# FSK_Receiver.net
KiCad netlist of a schematic drawn in Altium Designer
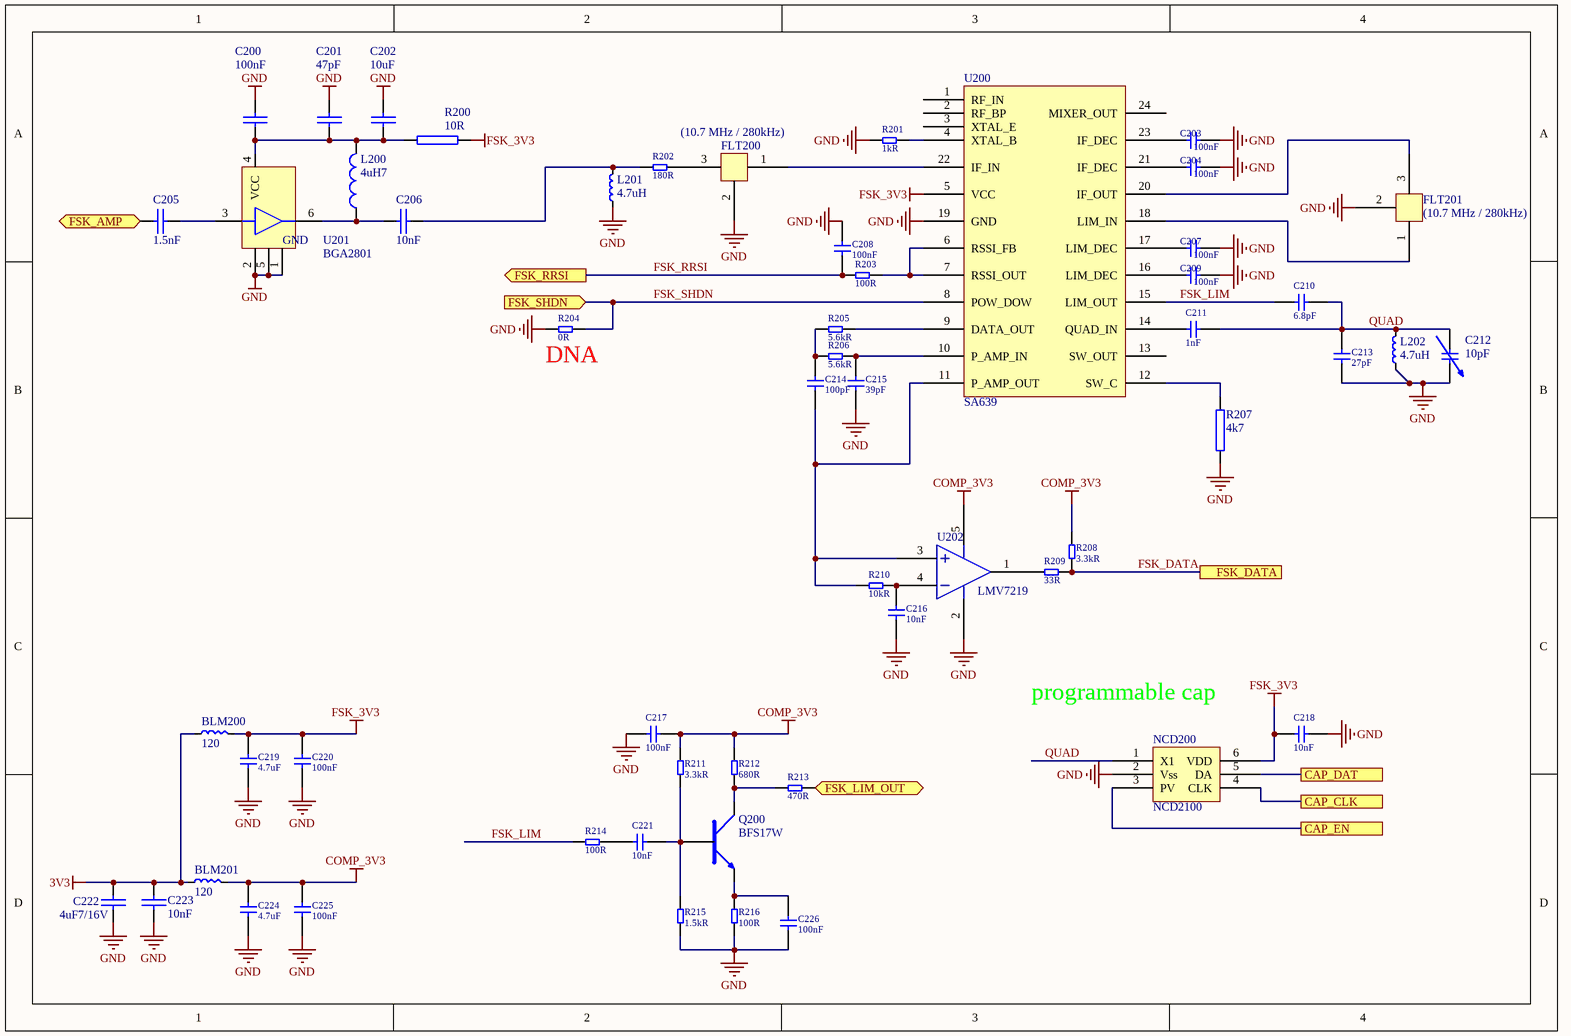
[diagram p0: FSK_Receiver.SchDoc]

(export (version "E")
  (design (tool "Eeschema 10.0.6"))
  (components
    (comp (ref "BLM200")
      (value "FerriteBeat")
      (footprint "BLM18SG121TN1")
      (description "BLM18SG121TN1")
      (fields (field (name "ALTIUM_UNNAMED_1") "120"))
      (libsource (lib "zynq_board") (part "FerriteBeat"))
    )
    (comp (ref "BLM201")
      (value "FerriteBeat")
      (footprint "BLM18SG121TN1")
      (description "BLM18SG121TN1")
      (fields (field (name "ALTIUM_UNNAMED_1") "120"))
      (libsource (lib "zynq_board") (part "FerriteBeat"))
    )
    (comp (ref "C200") (value "100nF") (footprint "0402RN") (libsource (lib "*") (part "_C")))
    (comp (ref "C201") (value "47pF") (footprint "0402RN") (libsource (lib "*") (part "_C")))
    (comp (ref "C202")
      (value "10uF")
      (footprint "0603R")
      (description "MLCC, X5R, 16V, 20%, 0603")
      (fields
        (field (name "PART NUMBER") "10u, 0603, 16V, X5R, 20%")
        (field (name "SOURCE") "SN29500-4, Tabelle 1")
      )
      (libsource (lib "Symeo_libs") (part "_CAP"))
    )
    (comp (ref "C203")
      (value "100nF")
      (footprint "C_SMD_0402")
      (description "100nF, 0402, 6.3V, 10%, X5R")
      (fields (field (name "Comment") "SMD capacitor"))
      (libsource (lib "zynq_board") (part "C_SMD"))
    )
    (comp (ref "C204")
      (value "100nF")
      (footprint "C_SMD_0402")
      (description "100nF, 0402, 6.3V, 10%, X5R")
      (fields (field (name "Comment") "SMD capacitor"))
      (libsource (lib "zynq_board") (part "C_SMD"))
    )
    (comp (ref "C205") (value "1.5nF") (footprint "0402RN") (libsource (lib "*") (part "_C")))
    (comp (ref "C206") (value "10nF") (footprint "0402RN") (libsource (lib "*") (part "_C")))
    (comp (ref "C207")
      (value "100nF")
      (footprint "C_SMD_0402")
      (description "100nF, 0402, 6.3V, 10%, X5R")
      (fields (field (name "Comment") "SMD capacitor"))
      (libsource (lib "zynq_board") (part "C_SMD"))
    )
    (comp (ref "C208")
      (value "100nF")
      (footprint "C_SMD_0402")
      (description "100nF, 0402, 6.3V, 10%, X5R")
      (fields (field (name "Comment") "SMD capacitor"))
      (libsource (lib "zynq_board") (part "C_SMD"))
    )
    (comp (ref "C209")
      (value "100nF")
      (footprint "C_SMD_0402")
      (description "100nF, 0402, 6.3V, 10%, X5R")
      (fields (field (name "Comment") "SMD capacitor"))
      (libsource (lib "zynq_board") (part "C_SMD"))
    )
    (comp (ref "C210")
      (value "6.8pF")
      (footprint "C_SMD_0402")
      (description "6.8pF, 0402, 6.3V, 10%, X5R")
      (fields (field (name "Comment") "SMD capacitor"))
      (libsource (lib "zynq_board") (part "C_SMD"))
    )
    (comp (ref "C211")
      (value "1nF")
      (footprint "C_SMD_0402")
      (description "1nF, 0402, 6.3V, 10%, X5R")
      (fields (field (name "Comment") "SMD capacitor"))
      (libsource (lib "zynq_board") (part "C_SMD"))
    )
    (comp (ref "C212")
      (value "10pF")
      (footprint "TZC03")
      (description "TZC03R100A110")
      (libsource (lib "zynq_board") (part "TZC03R100A110"))
    )
    (comp (ref "C213")
      (value "27pF")
      (footprint "C_SMD_0402")
      (description "28pF, 0402, 6.3V, 1%, X5R")
      (fields (field (name "Comment") "SMD capacitor"))
      (libsource (lib "zynq_board") (part "C_SMD"))
    )
    (comp (ref "C214")
      (value "100pF")
      (footprint "C_SMD_0402")
      (description "100pF, 0402, 6.3V, 10%, X5R")
      (fields (field (name "Comment") "SMD capacitor"))
      (libsource (lib "zynq_board") (part "C_SMD"))
    )
    (comp (ref "C215")
      (value "39pF")
      (footprint "C_SMD_0402")
      (description "39pF, 0402, 6.3V, 10%, X5R")
      (fields (field (name "Comment") "SMD capacitor"))
      (libsource (lib "zynq_board") (part "C_SMD"))
    )
    (comp (ref "C216")
      (value "10nF")
      (footprint "C_SMD_0402")
      (description "10nF, 0402, 6.3V, 10%, X5R")
      (fields (field (name "Comment") "SMD capacitor"))
      (libsource (lib "zynq_board") (part "C_SMD"))
    )
    (comp (ref "C217")
      (value "100nF")
      (footprint "C_SMD_0402")
      (description "100nF, 0402, 6.3V, 10%, X5R")
      (fields (field (name "Comment") "SMD capacitor"))
      (libsource (lib "zynq_board") (part "C_SMD"))
    )
    (comp (ref "C218")
      (value "10nF")
      (footprint "C_SMD_0402")
      (description "10nF, 0402, 6.3V, 10%, X5R")
      (fields (field (name "Comment") "SMD capacitor"))
      (libsource (lib "zynq_board") (part "C_SMD"))
    )
    (comp (ref "C219")
      (value "4.7uF")
      (footprint "C_SMD_0603")
      (description "4.7uF, 0603, 6.3V, 10%, X5R")
      (fields (field (name "Comment") "SMD capacitor"))
      (libsource (lib "zynq_board") (part "C_SMD"))
    )
    (comp (ref "C220")
      (value "100nF")
      (footprint "C_SMD_0402")
      (description "100nF, 0402, 6.3V, 10%, X5R")
      (fields (field (name "Comment") "SMD capacitor"))
      (libsource (lib "zynq_board") (part "C_SMD"))
    )
    (comp (ref "C221")
      (value "10nF")
      (footprint "C_SMD_0402")
      (description "10nF, 0402, 6.3V, 10%, X5R")
      (fields (field (name "Comment") "SMD capacitor"))
      (libsource (lib "zynq_board") (part "C_SMD"))
    )
    (comp (ref "C222")
      (value "4uF7/16V")
      (footprint "1206R")
      (description "MLCC, 1206, X7R, 16V, 20%")
      (fields (field (name "PART NUMBER") "4u7, 1206, 16V, X7R"))
      (libsource (lib "Symeo_libs") (part "_CAP"))
    )
    (comp (ref "C223")
      (value "10nF")
      (footprint "0402RN")
      (description "MLCC, X7R, 50V, 10%, 0402")
      (fields (field (name "PART NUMBER") "10n, 0402, 50V, X7R"))
      (libsource (lib "Symeo_libs") (part "_CAP"))
    )
    (comp (ref "C224")
      (value "4.7uF")
      (footprint "C_SMD_0603")
      (description "4.7uF, 0603, 6.3V, 10%, X5R")
      (fields (field (name "Comment") "SMD capacitor"))
      (libsource (lib "zynq_board") (part "C_SMD"))
    )
    (comp (ref "C225")
      (value "100nF")
      (footprint "C_SMD_0402")
      (description "100nF, 0402, 6.3V, 10%, X5R")
      (fields (field (name "Comment") "SMD capacitor"))
      (libsource (lib "zynq_board") (part "C_SMD"))
    )
    (comp (ref "C226")
      (value "100nF")
      (footprint "C_SMD_0402")
      (description "100nF, 0402, 6.3V, 10%, X5R")
      (fields (field (name "Comment") "SMD capacitor"))
      (libsource (lib "zynq_board") (part "C_SMD"))
    )
    (comp (ref "FLT200")
      (value "(10.7 MHz / 280kHz)")
      (footprint "Cerafil_10.7MHz_Filter")
      (description "Murata SFECV10M7FA00-R0")
      (libsource (lib "zynq_board") (part "CERAFIL_BP_10.7MHz"))
    )
    (comp (ref "FLT201")
      (value "(10.7 MHz / 280kHz)")
      (footprint "Cerafil_10.7MHz_Filter")
      (description "Murata SFECV10M7FA00-R0")
      (libsource (lib "") (part "CERAFIL_BP_10.7MHz_1"))
    )
    (comp (ref "L200")
      (value "4uH7")
      (footprint "0805R")
      (description "Wuerth WE MI; Wuerth Nr. 7447906")
      (libsource (lib "*") (part "_L"))
    )
    (comp (ref "L201")
      (value "4.7uH")
      (footprint "WE-MI SMD Multilayer Inductor")
      (description "7447906, WE Inductor")
      (libsource (lib "zynq_board") (part "7447906_L_4u7"))
    )
    (comp (ref "L202")
      (value "4.7uH")
      (footprint "WE-MI SMD Multilayer Inductor")
      (description "7447906, WE Inductor")
      (libsource (lib "zynq_board") (part "7447906_L_4u7"))
    )
    (comp (ref "NCD200")
      (value "~")
      (footprint "NCD2100:PCBComponent_1")
      (description "NCD2100 Non-volatile Digital Programmable Capacitor SOT23-6")
      (fields (field (name "PART NUMBER") "NCD2100"))
      (libsource (lib "Symeo_libs") (part "NCD2100"))
    )
    (comp (ref "Q200")
      (value "BFS17W")
      (footprint "SOT-323")
      (description "BFS17WH6327XTSA1")
      (libsource (lib "zynq_board") (part "BFS17W"))
    )
    (comp (ref "R200") (value "10R") (footprint "0402RN") (libsource (lib "*") (part "_R")))
    (comp (ref "R201")
      (value "1kR")
      (footprint "R_SMD_0402")
      (description "1kR, 0402, 1%")
      (fields (field (name "Comment") "SMD Resistor"))
      (libsource (lib "zynq_board") (part "R_SMD"))
    )
    (comp (ref "R202")
      (value "180R")
      (footprint "R_SMD_0402")
      (description "180R. 0402, 1%")
      (fields (field (name "Comment") "SMD Resistor"))
      (libsource (lib "zynq_board") (part "R_SMD"))
    )
    (comp (ref "R203")
      (value "100R")
      (footprint "R_SMD_0402")
      (description "100R, 0402, 1%")
      (fields (field (name "Comment") "SMD Resistor"))
      (libsource (lib "zynq_board") (part "R_SMD"))
    )
    (comp (ref "R204")
      (value "0R")
      (footprint "R_SMD_0402")
      (description "0R, 0402, 1%")
      (fields (field (name "Comment") "SMD Resistor"))
      (libsource (lib "zynq_board") (part "R_SMD"))
    )
    (comp (ref "R205")
      (value "5.6kR")
      (footprint "R_SMD_0402")
      (description "5.6kR, 0402, 1%")
      (fields (field (name "Comment") "SMD Resistor"))
      (libsource (lib "zynq_board") (part "R_SMD"))
    )
    (comp (ref "R206")
      (value "5.6kR")
      (footprint "R_SMD_0402")
      (description "5.6kR, 0402, 1%")
      (fields (field (name "Comment") "SMD Resistor"))
      (libsource (lib "zynq_board") (part "R_SMD"))
    )
    (comp (ref "R207")
      (value "4k7")
      (footprint "0402RN")
      (description "1%, 0.063W, 50V, 0402")
      (fields (field (name "PART NUMBER") "4k7, 0402, 1%, 0.063W, 50V"))
      (libsource (lib "Symeo_libs") (part "_RES"))
    )
    (comp (ref "R208")
      (value "3.3kR")
      (footprint "R_SMD_0402")
      (description "3.3kR, 0402, 1%")
      (fields (field (name "Comment") "SMD Resistor"))
      (libsource (lib "zynq_board") (part "R_SMD"))
    )
    (comp (ref "R209")
      (value "33R")
      (footprint "R_SMD_0402")
      (description "33R, 0402, 1%")
      (fields (field (name "Comment") "SMD Resistor"))
      (libsource (lib "zynq_board") (part "R_SMD"))
    )
    (comp (ref "R210")
      (value "10kR")
      (footprint "R_SMD_0402")
      (description "10kR, 0402, 1%")
      (fields (field (name "Comment") "SMD Resistor"))
      (libsource (lib "zynq_board") (part "R_SMD"))
    )
    (comp (ref "R211")
      (value "3.3kR")
      (footprint "R_SMD_0402")
      (description "3.3kR, 0402, 1%")
      (fields (field (name "Comment") "SMD Resistor"))
      (libsource (lib "zynq_board") (part "R_SMD"))
    )
    (comp (ref "R212")
      (value "680R")
      (footprint "R_SMD_0402")
      (description "680R, 0402, 1%")
      (fields (field (name "Comment") "SMD Resistor"))
      (libsource (lib "zynq_board") (part "R_SMD"))
    )
    (comp (ref "R213")
      (value "470R")
      (footprint "R_SMD_0402")
      (description "470R, 0402, 1%")
      (fields (field (name "Comment") "SMD Resistor"))
      (libsource (lib "zynq_board") (part "R_SMD"))
    )
    (comp (ref "R214")
      (value "100R")
      (footprint "R_SMD_0402")
      (description "100R, 0402, 1%")
      (fields (field (name "Comment") "SMD Resistor"))
      (libsource (lib "zynq_board") (part "R_SMD"))
    )
    (comp (ref "R215")
      (value "1.5kR")
      (footprint "R_SMD_0402")
      (description "1.5kR, 0402, 1%")
      (fields (field (name "Comment") "SMD Resistor"))
      (libsource (lib "zynq_board") (part "R_SMD"))
    )
    (comp (ref "R216")
      (value "100R")
      (footprint "R_SMD_0402")
      (description "100R, 0402, 1%")
      (fields (field (name "Comment") "SMD Resistor"))
      (libsource (lib "zynq_board") (part "R_SMD"))
    )
    (comp (ref "U200")
      (value "SA639")
      (footprint "TSSOP24")
      (description "SA639DH/01,118")
      (libsource (lib "zynq_board") (part "SA639"))
    )
    (comp (ref "U201")
      (value "BGA2801")
      (footprint "SOT-363:SOT-363")
      (description "NXP BGA2801")
      (libsource (lib "AVAGO_RF") (part "ABA-32563"))
    )
    (comp (ref "U202")
      (value "LMV7219")
      (footprint "SOT-23-5")
      (description "LMV7219M5")
      (libsource (lib "zynq_board") (part "LMV7219"))
    )
  )
  (nets
    (net (code "1") (name "/CAP_CLK") (class "Default")
      (node (ref "NCD200") (pin "4") (pinfunction "CLK_4") (pintype "passive"))
    )
    (net (code "2") (name "/CAP_DAT") (class "Default")
      (node (ref "NCD200") (pin "5") (pinfunction "DA_5") (pintype "passive"))
    )
    (net (code "3") (name "/CAP_EN") (class "Default")
      (node (ref "NCD200") (pin "3") (pinfunction "PV_3") (pintype "passive"))
    )
    (net (code "4") (name "/FSK_AMP") (class "Default") (node (ref "C205") (pin "2") (pintype "passive")))
    (net (code "5") (name "/FSK_DATA") (class "Default")
      (node (ref "R208") (pin "2") (pinfunction "2_2") (pintype "passive"))
      (node (ref "R209") (pin "1") (pinfunction "1_1") (pintype "passive"))
    )
    (net (code "6") (name "/FSK_LIM") (class "Default")
      (node (ref "C210") (pin "1") (pinfunction "1_1") (pintype "passive"))
      (node (ref "R214") (pin "2") (pinfunction "2_2") (pintype "passive"))
      (node (ref "U200") (pin "15") (pinfunction "LIM_OUT_15") (pintype "passive"))
    )
    (net (code "7") (name "/FSK_LIM_OUT") (class "Default")
      (node (ref "R213") (pin "2") (pinfunction "2_2") (pintype "passive"))
    )
    (net (code "8") (name "/FSK_RRSI") (class "Default")
      (node (ref "C208") (pin "2") (pinfunction "2_2") (pintype "passive"))
      (node (ref "R203") (pin "2") (pinfunction "2_2") (pintype "passive"))
    )
    (net (code "9") (name "/FSK_SHDN") (class "Default")
      (node (ref "R204") (pin "1") (pinfunction "1_1") (pintype "passive"))
      (node (ref "U200") (pin "8") (pinfunction "POW_DOW_8") (pintype "passive"))
    )
    (net (code "10") (name "/QUAD") (class "Default")
      (node (ref "C210") (pin "2") (pinfunction "2_2") (pintype "passive"))
      (node (ref "C211") (pin "2") (pinfunction "2_2") (pintype "passive"))
      (node (ref "C212") (pin "1") (pinfunction "1_1") (pintype "passive"))
      (node (ref "C213") (pin "2") (pinfunction "2_2") (pintype "passive"))
      (node (ref "L202") (pin "1") (pinfunction "1_1") (pintype "passive"))
      (node (ref "NCD200") (pin "1") (pinfunction "X1_1") (pintype "passive"))
    )
    (net (code "11") (name "3V3") (class "Default")
      (node (ref "BLM200") (pin "2") (pinfunction "2_2") (pintype "passive"))
      (node (ref "BLM201") (pin "2") (pinfunction "2_2") (pintype "passive"))
      (node (ref "C222") (pin "1") (pintype "passive"))
      (node (ref "C223") (pin "1") (pintype "passive"))
    )
    (net (code "12") (name "COMP_3V3") (class "Default")
      (node (ref "BLM201") (pin "1") (pinfunction "1_1") (pintype "passive"))
      (node (ref "C217") (pin "2") (pinfunction "2_2") (pintype "passive"))
      (node (ref "C224") (pin "1") (pinfunction "1_1") (pintype "passive"))
      (node (ref "C225") (pin "1") (pinfunction "1_1") (pintype "passive"))
      (node (ref "R208") (pin "1") (pinfunction "1_1") (pintype "passive"))
      (node (ref "R211") (pin "1") (pinfunction "1_1") (pintype "passive"))
      (node (ref "R212") (pin "1") (pinfunction "1_1") (pintype "passive"))
      (node (ref "U202") (pin "5") (pintype "passive"))
    )
    (net (code "13") (name "FSK_3V3") (class "Default")
      (node (ref "BLM200") (pin "1") (pinfunction "1_1") (pintype "passive"))
      (node (ref "C218") (pin "2") (pinfunction "2_2") (pintype "passive"))
      (node (ref "C219") (pin "1") (pinfunction "1_1") (pintype "passive"))
      (node (ref "C220") (pin "1") (pinfunction "1_1") (pintype "passive"))
      (node (ref "NCD200") (pin "6") (pinfunction "VDD_6") (pintype "passive"))
      (node (ref "R200") (pin "2") (pintype "passive"))
      (node (ref "U200") (pin "5") (pinfunction "VCC_5") (pintype "passive"))
    )
    (net (code "14") (name "GND") (class "Default")
      (node (ref "C200") (pin "2") (pintype "passive"))
      (node (ref "C201") (pin "2") (pintype "passive"))
      (node (ref "C202") (pin "1") (pintype "passive"))
      (node (ref "C203") (pin "2") (pinfunction "2_2") (pintype "passive"))
      (node (ref "C204") (pin "2") (pinfunction "2_2") (pintype "passive"))
      (node (ref "C207") (pin "2") (pinfunction "2_2") (pintype "passive"))
      (node (ref "C208") (pin "1") (pinfunction "1_1") (pintype "passive"))
      (node (ref "C209") (pin "2") (pinfunction "2_2") (pintype "passive"))
      (node (ref "C212") (pin "2") (pinfunction "2_2") (pintype "passive"))
      (node (ref "C213") (pin "1") (pinfunction "1_1") (pintype "passive"))
      (node (ref "C215") (pin "2") (pinfunction "2_2") (pintype "passive"))
      (node (ref "C216") (pin "2") (pinfunction "2_2") (pintype "passive"))
      (node (ref "C217") (pin "1") (pinfunction "1_1") (pintype "passive"))
      (node (ref "C218") (pin "1") (pinfunction "1_1") (pintype "passive"))
      (node (ref "C219") (pin "2") (pinfunction "2_2") (pintype "passive"))
      (node (ref "C220") (pin "2") (pinfunction "2_2") (pintype "passive"))
      (node (ref "C222") (pin "2") (pintype "passive"))
      (node (ref "C223") (pin "2") (pintype "passive"))
      (node (ref "C224") (pin "2") (pinfunction "2_2") (pintype "passive"))
      (node (ref "C225") (pin "2") (pinfunction "2_2") (pintype "passive"))
      (node (ref "C226") (pin "2") (pinfunction "2_2") (pintype "passive"))
      (node (ref "FLT200") (pin "2") (pintype "passive"))
      (node (ref "FLT201") (pin "2") (pintype "passive"))
      (node (ref "L201") (pin "2") (pinfunction "2_2") (pintype "passive"))
      (node (ref "L202") (pin "2") (pinfunction "2_2") (pintype "passive"))
      (node (ref "NCD200") (pin "2") (pinfunction "Vss_2") (pintype "passive"))
      (node (ref "R201") (pin "2") (pinfunction "2_2") (pintype "passive"))
      (node (ref "R204") (pin "2") (pinfunction "2_2") (pintype "passive"))
      (node (ref "R207") (pin "1") (pintype "passive"))
      (node (ref "R215") (pin "2") (pinfunction "2_2") (pintype "passive"))
      (node (ref "R216") (pin "2") (pinfunction "2_2") (pintype "passive"))
      (node (ref "U200") (pin "19") (pinfunction "GND_19") (pintype "passive"))
      (node (ref "U201") (pin "1") (pintype "passive"))
      (node (ref "U201") (pin "2") (pintype "passive"))
      (node (ref "U201") (pin "5") (pintype "passive"))
      (node (ref "U202") (pin "2") (pintype "passive"))
    )
    (net (code "15") (name "Net-(C203-Pad1)") (class "Default")
      (node (ref "C203") (pin "1") (pinfunction "1_1") (pintype "passive"))
      (node (ref "U200") (pin "23") (pinfunction "IF_DEC_23") (pintype "passive"))
    )
    (net (code "16") (name "Net-(C204-Pad1)") (class "Default")
      (node (ref "C204") (pin "1") (pinfunction "1_1") (pintype "passive"))
      (node (ref "U200") (pin "21") (pinfunction "IF_DEC_21") (pintype "passive"))
    )
    (net (code "17") (name "Net-(C205-Pad1)") (class "Default")
      (node (ref "C205") (pin "1") (pintype "passive"))
      (node (ref "U201") (pin "3") (pintype "passive"))
    )
    (net (code "18") (name "Net-(C206-Pad1)") (class "Default")
      (node (ref "C206") (pin "1") (pintype "passive"))
      (node (ref "L200") (pin "1") (pinfunction "1_1") (pintype "passive"))
      (node (ref "U201") (pin "6") (pintype "passive"))
    )
    (net (code "19") (name "Net-(C206-Pad2)") (class "Default")
      (node (ref "C206") (pin "2") (pintype "passive"))
      (node (ref "L201") (pin "1") (pinfunction "1_1") (pintype "passive"))
      (node (ref "R202") (pin "2") (pinfunction "2_2") (pintype "passive"))
    )
    (net (code "20") (name "Net-(C207-Pad1)") (class "Default")
      (node (ref "C207") (pin "1") (pinfunction "1_1") (pintype "passive"))
      (node (ref "U200") (pin "17") (pinfunction "LIM_DEC_17") (pintype "passive"))
    )
    (net (code "21") (name "Net-(C209-Pad1)") (class "Default")
      (node (ref "C209") (pin "1") (pinfunction "1_1") (pintype "passive"))
      (node (ref "U200") (pin "16") (pinfunction "LIM_DEC_16") (pintype "passive"))
    )
    (net (code "22") (name "Net-(C214-Pad1)") (class "Default")
      (node (ref "C214") (pin "1") (pinfunction "1_1") (pintype "passive"))
      (node (ref "R205") (pin "2") (pinfunction "2_2") (pintype "passive"))
      (node (ref "R206") (pin "2") (pinfunction "2_2") (pintype "passive"))
    )
    (net (code "23") (name "Net-(C216-Pad1)") (class "Default")
      (node (ref "C216") (pin "1") (pinfunction "1_1") (pintype "passive"))
      (node (ref "R210") (pin "1") (pinfunction "1_1") (pintype "passive"))
      (node (ref "U202") (pin "4") (pintype "passive"))
    )
    (net (code "24") (name "Net-(C221-Pad1)") (class "Default")
      (node (ref "C221") (pin "1") (pinfunction "1_1") (pintype "passive"))
      (node (ref "R214") (pin "1") (pinfunction "1_1") (pintype "passive"))
    )
    (net (code "25") (name "Net-(FLT200-Pad3)") (class "Default")
      (node (ref "FLT200") (pin "3") (pintype "passive"))
      (node (ref "R202") (pin "1") (pinfunction "1_1") (pintype "passive"))
    )
    (net (code "26") (name "Net-(Q200-B)") (class "Default")
      (node (ref "C221") (pin "2") (pinfunction "2_2") (pintype "passive"))
      (node (ref "Q200") (pin "1") (pinfunction "B_1") (pintype "passive"))
      (node (ref "R211") (pin "2") (pinfunction "2_2") (pintype "passive"))
      (node (ref "R215") (pin "1") (pinfunction "1_1") (pintype "passive"))
    )
    (net (code "27") (name "Net-(Q200-C)") (class "Default")
      (node (ref "Q200") (pin "3") (pinfunction "C_3") (pintype "passive"))
      (node (ref "R212") (pin "2") (pinfunction "2_2") (pintype "passive"))
      (node (ref "R213") (pin "1") (pinfunction "1_1") (pintype "passive"))
    )
    (net (code "28") (name "Net-(Q200-E)") (class "Default")
      (node (ref "C226") (pin "1") (pinfunction "1_1") (pintype "passive"))
      (node (ref "Q200") (pin "2") (pinfunction "E_2") (pintype "passive"))
      (node (ref "R216") (pin "1") (pinfunction "1_1") (pintype "passive"))
    )
    (net (code "29") (name "Net-(R209-Pad2)") (class "Default")
      (node (ref "R209") (pin "2") (pinfunction "2_2") (pintype "passive"))
      (node (ref "U202") (pin "1") (pintype "passive"))
    )
    (net (code "30") (name "Net-(U200-DATA_OUT)") (class "Default")
      (node (ref "R205") (pin "1") (pinfunction "1_1") (pintype "passive"))
      (node (ref "U200") (pin "9") (pinfunction "DATA_OUT_9") (pintype "passive"))
    )
    (net (code "31") (name "Net-(U200-IF_IN)") (class "Default")
      (node (ref "FLT200") (pin "1") (pintype "passive"))
      (node (ref "U200") (pin "22") (pinfunction "IF_IN_22") (pintype "passive"))
    )
    (net (code "32") (name "Net-(U200-IF_OUT)") (class "Default")
      (node (ref "FLT201") (pin "3") (pintype "passive"))
      (node (ref "U200") (pin "20") (pinfunction "IF_OUT_20") (pintype "passive"))
    )
    (net (code "33") (name "Net-(U200-LIM_IN)") (class "Default")
      (node (ref "FLT201") (pin "1") (pintype "passive"))
      (node (ref "U200") (pin "18") (pinfunction "LIM_IN_18") (pintype "passive"))
    )
    (net (code "34") (name "Net-(U200-P_AMP_IN)") (class "Default")
      (node (ref "C215") (pin "1") (pinfunction "1_1") (pintype "passive"))
      (node (ref "R206") (pin "1") (pinfunction "1_1") (pintype "passive"))
      (node (ref "U200") (pin "10") (pinfunction "P_AMP_IN_10") (pintype "passive"))
    )
    (net (code "35") (name "Net-(U200-P_AMP_OUT)") (class "Default")
      (node (ref "C214") (pin "2") (pinfunction "2_2") (pintype "passive"))
      (node (ref "R210") (pin "2") (pinfunction "2_2") (pintype "passive"))
      (node (ref "U200") (pin "11") (pinfunction "P_AMP_OUT_11") (pintype "passive"))
      (node (ref "U202") (pin "3") (pintype "passive"))
    )
    (net (code "36") (name "Net-(U200-QUAD_IN)") (class "Default")
      (node (ref "C211") (pin "1") (pinfunction "1_1") (pintype "passive"))
      (node (ref "U200") (pin "14") (pinfunction "QUAD_IN_14") (pintype "passive"))
    )
    (net (code "37") (name "Net-(U200-RSSI_FB)") (class "Default")
      (node (ref "R203") (pin "1") (pinfunction "1_1") (pintype "passive"))
      (node (ref "U200") (pin "6") (pinfunction "RSSI_FB_6") (pintype "passive"))
      (node (ref "U200") (pin "7") (pinfunction "RSSI_OUT_7") (pintype "passive"))
    )
    (net (code "38") (name "Net-(U200-SW_C)") (class "Default")
      (node (ref "R207") (pin "2") (pintype "passive"))
      (node (ref "U200") (pin "12") (pinfunction "SW_C_12") (pintype "passive"))
    )
    (net (code "39") (name "Net-(U200-XTAL_B)") (class "Default")
      (node (ref "R201") (pin "1") (pinfunction "1_1") (pintype "passive"))
      (node (ref "U200") (pin "4") (pinfunction "XTAL_B_4") (pintype "passive"))
    )
    (net (code "40") (name "Net-(U201-VCC)") (class "Default")
      (node (ref "C200") (pin "1") (pintype "passive"))
      (node (ref "C201") (pin "1") (pintype "passive"))
      (node (ref "C202") (pin "2") (pintype "passive"))
      (node (ref "L200") (pin "2") (pinfunction "2_2") (pintype "passive"))
      (node (ref "R200") (pin "1") (pintype "passive"))
      (node (ref "U201") (pin "4") (pinfunction "VCC_4") (pintype "passive"))
    )
    (net (code "41") (name "unconnected-(U200-MIXER_OUT-Pad24)") (class "Default")
      (node (ref "U200") (pin "24") (pinfunction "MIXER_OUT_24") (pintype "passive"))
    )
    (net (code "42") (name "unconnected-(U200-RF_BP-Pad2)") (class "Default")
      (node (ref "U200") (pin "2") (pinfunction "RF_BP_2") (pintype "passive"))
    )
    (net (code "43") (name "unconnected-(U200-RF_IN-Pad1)") (class "Default")
      (node (ref "U200") (pin "1") (pinfunction "RF_IN_1") (pintype "passive"))
    )
    (net (code "44") (name "unconnected-(U200-SW_OUT-Pad13)") (class "Default")
      (node (ref "U200") (pin "13") (pinfunction "SW_OUT_13") (pintype "passive"))
    )
    (net (code "45") (name "unconnected-(U200-XTAL_E-Pad3)") (class "Default")
      (node (ref "U200") (pin "3") (pinfunction "XTAL_E_3") (pintype "passive"))
    )
  )
)
